# 100_ESP.net
KiCad netlist of a schematic drawn in Altium Designer
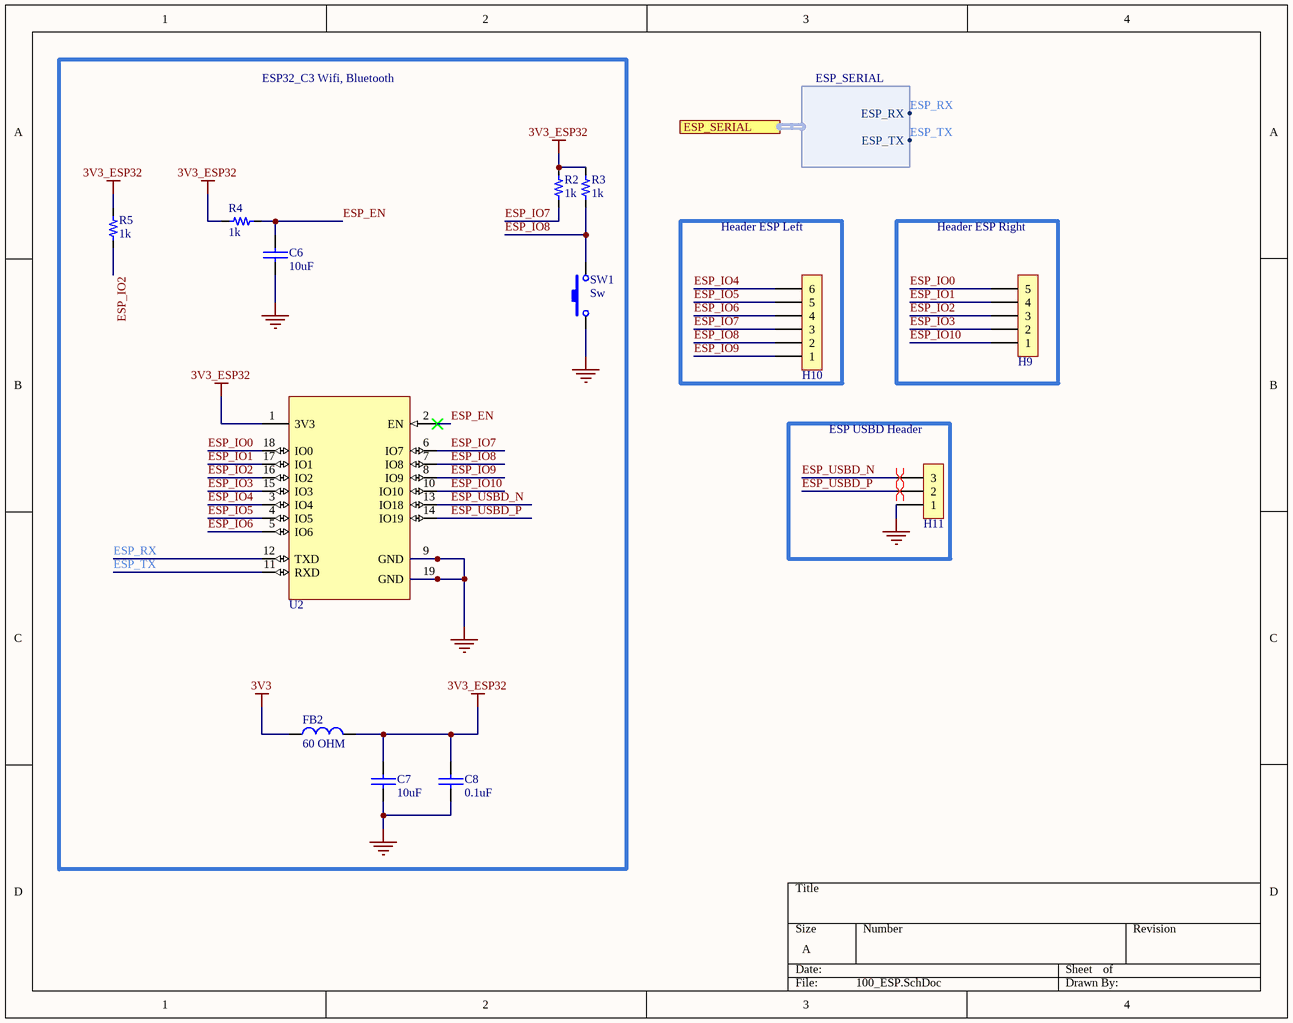
[diagram p0: 100_ESP.SchDoc]

(export (version "E")
  (design (tool "Eeschema 10.0.6"))
  (components
    (comp (ref "C6")
      (value "10uF")
      (footprint "0805_cap")
      (description "25V 10uF X5R ±10% 0805 Multilayer Ceramic Capacitors MLCC - SMD/SMT ROHS")
      (fields
        (field (name "MANUFACTURER") "Samsung Electro-Mechanics")
        (field (name "MANUFACTURER PART NUMBER") "CL21A106KAYNNNE")
      )
      (libsource (lib "shared_lib") (part "Cap_10uF_0805_25V_"))
    )
    (comp (ref "C7")
      (value "10uF")
      (footprint "0805_cap")
      (description "25V 10uF X5R ±10% 0805 Multilayer Ceramic Capacitors MLCC - SMD/SMT ROHS")
      (fields
        (field (name "MANUFACTURER") "Samsung Electro-Mechanics")
        (field (name "MANUFACTURER PART NUMBER") "CL21A106KAYNNNE")
      )
      (libsource (lib "shared_lib") (part "Cap_10uF_0805_25V_"))
    )
    (comp (ref "C8")
      (value "0.1uF")
      (footprint "0603_cap")
      (description "50V 100nF Y5V -20%~+80% 0603 Multilayer Ceramic Capacitors MLCC - SMD/SMT ROHS")
      (fields
        (field (name "MANUFACTURER") "Walsin Tech Corp")
        (field (name "MANUFACTURER PART NUMBER") "0603F104Z500CT")
      )
      (libsource (lib "shared_lib") (part "Cap_0.1uF_0603_50V"))
    )
    (comp (ref "FB2")
      (value "60 OHM")
      (footprint "0603_fb")
      (description "2A 1 100mΩ 60Ω@100MHz ±25% 0603 Ferrite Beads ROHS")
      (fields
        (field (name "MANUFACTURER") "TAI-TECH")
        (field (name "MANUFACTURER PART NUMBER") "HCB1608KF-600T20")
      )
      (libsource (lib "shared_lib") (part "FB_60_0603_2A"))
    )
    (comp (ref "H9")
      (value "5x1")
      (footprint "H_5x1_TH_100mil")
      (description "H_Male_5x1_TH_100mil")
      (libsource (lib "shared_lib") (part "H_Male_5x1_TH_100mil"))
    )
    (comp (ref "H10")
      (value "6x1")
      (footprint "H_6x1_TH_100mil")
      (description "H_Male_6x1_TH_100mil")
      (libsource (lib "shared_lib") (part "H_Male_6x1_TH_100mil"))
    )
    (comp (ref "H11")
      (value "3x1")
      (footprint "H_3X1_TH_100mil")
      (description "H_Male_3x1_TH_100mil")
      (libsource (lib "shared_lib") (part "H_Male_3x1_TH_100mil"))
    )
    (comp (ref "R2")
      (value "1k")
      (footprint "0603_res")
      (description "RES SMD 1k OHM 5% 1/10W 0603")
      (fields
        (field (name "MANUFACTURER") "FOJAN")
        (field (name "MANUFACTURER PART NUMBER") "FRC0603J102 TS")
      )
      (libsource (lib "shared_lib") (part "Res_1k_0603_1/10W"))
    )
    (comp (ref "R3")
      (value "1k")
      (footprint "0603_res")
      (description "RES SMD 1k OHM 5% 1/10W 0603")
      (fields
        (field (name "MANUFACTURER") "FOJAN")
        (field (name "MANUFACTURER PART NUMBER") "FRC0603J102 TS")
      )
      (libsource (lib "shared_lib") (part "Res_1k_0603_1/10W"))
    )
    (comp (ref "R4")
      (value "1k")
      (footprint "0603_res")
      (description "RES SMD 1k OHM 5% 1/10W 0603")
      (fields
        (field (name "MANUFACTURER") "FOJAN")
        (field (name "MANUFACTURER PART NUMBER") "FRC0603J102 TS")
      )
      (libsource (lib "shared_lib") (part "Res_1k_0603_1/10W"))
    )
    (comp (ref "R5")
      (value "1k")
      (footprint "0603_res")
      (description "RES SMD 1k OHM 5% 1/10W 0603")
      (fields
        (field (name "MANUFACTURER") "FOJAN")
        (field (name "MANUFACTURER PART NUMBER") "FRC0603J102 TS")
      )
      (libsource (lib "shared_lib") (part "Res_1k_0603_1/10W"))
    )
    (comp (ref "SW1")
      (value "Sw")
      (footprint "Sw_PUSH_4.5x4.5x5mm")
      (description "SWITCH TACTILE SPST-NO 0.05A 12V")
      (fields
        (field (name "MANUFACTURER") "BZCN")
        (field (name "MANUFACTURER PART NUMBER") "TSC015A05026A")
        (field (name "LAST MODIFIED BY") "N-A.Potosi")
      )
      (libsource (lib "shared_lib") (part "Sw_PUSH_4.5x4.5x5.0xmm"))
    )
    (comp (ref "U2")
      (value "ESP32-C3-WROOM-02-N4")
      (footprint "ESP32-C3-WROOM-02-N4")
      (description "RF TXRX MOD BT WIFI PCB TH SMD")
      (fields (field (name "MANUFACTURER") "Espressif Systems"))
      (libsource (lib "shared_lib") (part "MCU_ESP32-C3-WROOM-02-N4"))
    )
  )
  (nets
    (net (code "2") (name "/ESP_EN") (class "Default")
      (node (ref "C6") (pin "1") (pinfunction "1_1") (pintype "passive"))
      (node (ref "R4") (pin "1") (pinfunction "1_1") (pintype "passive"))
      (node (ref "U2") (pin "2") (pinfunction "EN_2") (pintype "input"))
    )
    (net (code "3") (name "/ESP_IO0") (class "Default")
      (node (ref "H9") (pin "5") (pinfunction "5_5") (pintype "passive"))
      (node (ref "U2") (pin "18") (pinfunction "IO0_18") (pintype "bidirectional"))
    )
    (net (code "4") (name "/ESP_IO1") (class "Default")
      (node (ref "H9") (pin "4") (pinfunction "4_4") (pintype "passive"))
      (node (ref "U2") (pin "17") (pinfunction "IO1_17") (pintype "bidirectional"))
    )
    (net (code "5") (name "/ESP_IO2") (class "Default")
      (node (ref "H9") (pin "3") (pinfunction "3_3") (pintype "passive"))
      (node (ref "R5") (pin "1") (pinfunction "1_1") (pintype "passive"))
      (node (ref "U2") (pin "16") (pinfunction "IO2_16") (pintype "bidirectional"))
    )
    (net (code "6") (name "/ESP_IO3") (class "Default")
      (node (ref "H9") (pin "2") (pinfunction "2_2") (pintype "passive"))
      (node (ref "U2") (pin "15") (pinfunction "IO3_15") (pintype "bidirectional"))
    )
    (net (code "7") (name "/ESP_IO4") (class "Default")
      (node (ref "H10") (pin "6") (pinfunction "6_6") (pintype "passive"))
      (node (ref "U2") (pin "3") (pinfunction "IO4_3") (pintype "bidirectional"))
    )
    (net (code "8") (name "/ESP_IO5") (class "Default")
      (node (ref "H10") (pin "5") (pinfunction "5_5") (pintype "passive"))
      (node (ref "U2") (pin "4") (pinfunction "IO5_4") (pintype "bidirectional"))
    )
    (net (code "9") (name "/ESP_IO6") (class "Default")
      (node (ref "H10") (pin "4") (pinfunction "4_4") (pintype "passive"))
      (node (ref "U2") (pin "5") (pinfunction "IO6_5") (pintype "bidirectional"))
    )
    (net (code "10") (name "/ESP_IO7") (class "Default")
      (node (ref "H10") (pin "3") (pinfunction "3_3") (pintype "passive"))
      (node (ref "R2") (pin "1") (pinfunction "1_1") (pintype "passive"))
      (node (ref "U2") (pin "6") (pinfunction "IO7_6") (pintype "bidirectional"))
    )
    (net (code "11") (name "/ESP_IO8") (class "Default")
      (node (ref "H10") (pin "2") (pinfunction "2_2") (pintype "passive"))
      (node (ref "R3") (pin "1") (pinfunction "1_1") (pintype "passive"))
      (node (ref "SW1") (pin "2") (pinfunction "2_2") (pintype "passive"))
      (node (ref "U2") (pin "7") (pinfunction "IO8_7") (pintype "bidirectional"))
    )
    (net (code "12") (name "/ESP_IO9") (class "Default")
      (node (ref "H10") (pin "1") (pinfunction "1_1") (pintype "passive"))
      (node (ref "U2") (pin "8") (pinfunction "IO9_8") (pintype "bidirectional"))
    )
    (net (code "13") (name "/ESP_IO10") (class "Default")
      (node (ref "H9") (pin "1") (pinfunction "1_1") (pintype "passive"))
      (node (ref "U2") (pin "10") (pinfunction "IO10_10") (pintype "bidirectional"))
    )
    (net (code "14") (name "/ESP_RX") (class "Default")
      (node (ref "U2") (pin "12") (pinfunction "TXD_12") (pintype "bidirectional"))
    )
    (net (code "15") (name "/ESP_TX") (class "Default")
      (node (ref "U2") (pin "11") (pinfunction "RXD_11") (pintype "bidirectional"))
    )
    (net (code "16") (name "/ESP_USBD_N") (class "Default")
      (node (ref "H11") (pin "3") (pinfunction "3_3") (pintype "passive"))
      (node (ref "U2") (pin "13") (pinfunction "IO18_13") (pintype "bidirectional"))
    )
    (net (code "17") (name "/ESP_USBD_P") (class "Default")
      (node (ref "H11") (pin "2") (pinfunction "2_2") (pintype "passive"))
      (node (ref "U2") (pin "14") (pinfunction "IO19_14") (pintype "bidirectional"))
    )
    (net (code "19") (name "3V3") (class "Default")
      (node (ref "FB2") (pin "1") (pinfunction "1_1") (pintype "passive"))
    )
    (net (code "20") (name "3V3_ESP32") (class "Default")
      (node (ref "C7") (pin "1") (pinfunction "1_1") (pintype "passive"))
      (node (ref "C8") (pin "1") (pinfunction "1_1") (pintype "passive"))
      (node (ref "FB2") (pin "2") (pinfunction "2_2") (pintype "passive"))
      (node (ref "R2") (pin "2") (pinfunction "2_2") (pintype "passive"))
      (node (ref "R3") (pin "2") (pinfunction "2_2") (pintype "passive"))
      (node (ref "R4") (pin "2") (pinfunction "2_2") (pintype "passive"))
      (node (ref "R5") (pin "2") (pinfunction "2_2") (pintype "passive"))
      (node (ref "U2") (pin "1") (pinfunction "3V3_1") (pintype "power_in"))
    )
    (net (code "21") (name "GND") (class "Default")
      (node (ref "C6") (pin "2") (pinfunction "2_2") (pintype "passive"))
      (node (ref "C7") (pin "2") (pinfunction "2_2") (pintype "passive"))
      (node (ref "C8") (pin "2") (pinfunction "2_2") (pintype "passive"))
      (node (ref "H11") (pin "1") (pinfunction "1_1") (pintype "passive"))
      (node (ref "SW1") (pin "1") (pinfunction "1_1") (pintype "passive"))
      (node (ref "U2") (pin "19") (pinfunction "GND_19") (pintype "power_in"))
      (node (ref "U2") (pin "9") (pinfunction "GND_9") (pintype "power_in"))
    )
  )
)
